# USB_Audio.net
KiCad netlist of a schematic drawn in Altium Designer
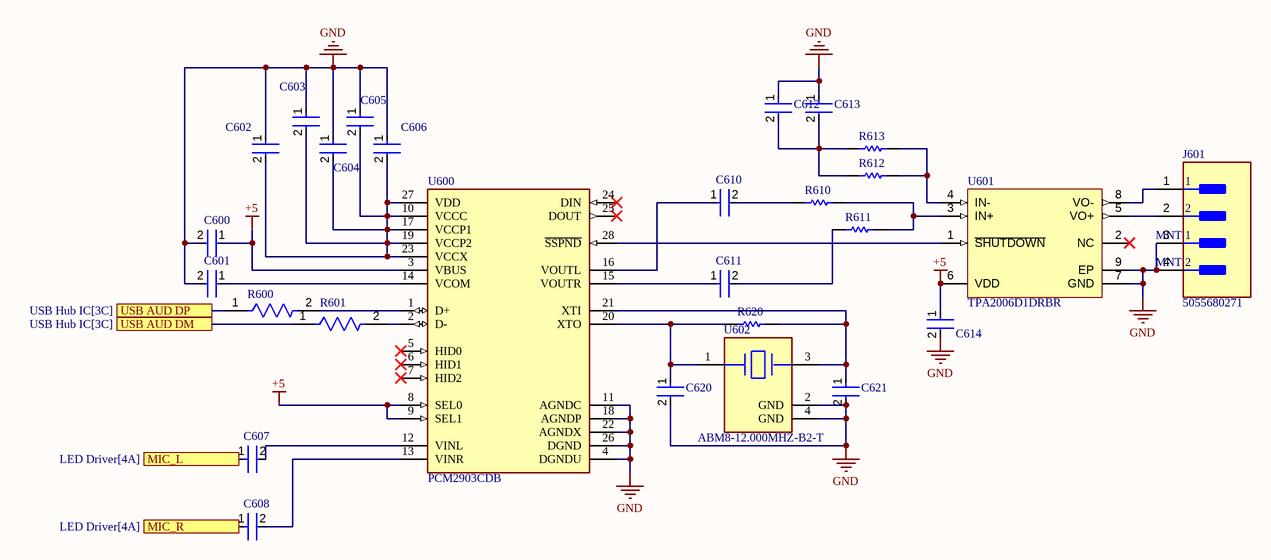
[diagram p0: USB Audio.SchDoc]

(export (version "E")
  (design (tool "Eeschema 10.0.6"))
  (components
    (comp (ref "C600")
      (value "GRM155R70J105KA12D")
      (footprint "FP-GRM155-0_05-MFG")
      (description "Chip Multilayer Ceramic Capacitors for General Purpose, 0402, 1.0uF, X7R, 15%, 10%, 6.3V")
      (fields (field (name "TOLERANCE") "10%"))
      (libsource (lib "Altium Content Vault") (part "02cd4be3c70576c341d710602a673aa"))
    )
    (comp (ref "C601")
      (value "GRM155R70J105KA12D")
      (footprint "FP-GRM155-0_05-MFG")
      (description "Chip Multilayer Ceramic Capacitors for General Purpose, 0402, 1.0uF, X7R, 15%, 10%, 6.3V")
      (fields (field (name "TOLERANCE") "10%"))
      (libsource (lib "Altium Content Vault") (part "02cd4be3c70576c341d710602a673aa"))
    )
    (comp (ref "C602")
      (value "GRM155R70J105KA12D")
      (footprint "FP-GRM155-0_05-MFG")
      (description "Chip Multilayer Ceramic Capacitors for General Purpose, 0402, 1.0uF, X7R, 15%, 10%, 6.3V")
      (fields (field (name "TOLERANCE") "10%"))
      (libsource (lib "Altium Content Vault") (part "02cd4be3c70576c341d710602a673aa"))
    )
    (comp (ref "C603")
      (value "GRM155R70J105KA12D")
      (footprint "FP-GRM155-0_05-MFG")
      (description "Chip Multilayer Ceramic Capacitors for General Purpose, 0402, 1.0uF, X7R, 15%, 10%, 6.3V")
      (fields (field (name "TOLERANCE") "10%"))
      (libsource (lib "Altium Content Vault") (part "02cd4be3c70576c341d710602a673aa"))
    )
    (comp (ref "C604")
      (value "GRM155R70J105KA12D")
      (footprint "FP-GRM155-0_05-MFG")
      (description "Chip Multilayer Ceramic Capacitors for General Purpose, 0402, 1.0uF, X7R, 15%, 10%, 6.3V")
      (fields (field (name "TOLERANCE") "10%"))
      (libsource (lib "Altium Content Vault") (part "02cd4be3c70576c341d710602a673aa"))
    )
    (comp (ref "C605")
      (value "GRM155R70J105KA12D")
      (footprint "FP-GRM155-0_05-MFG")
      (description "Chip Multilayer Ceramic Capacitors for General Purpose, 0402, 1.0uF, X7R, 15%, 10%, 6.3V")
      (fields (field (name "TOLERANCE") "10%"))
      (libsource (lib "Altium Content Vault") (part "02cd4be3c70576c341d710602a673aa"))
    )
    (comp (ref "C606")
      (value "GRM155R70J105KA12D")
      (footprint "FP-GRM155-0_05-MFG")
      (description "Chip Multilayer Ceramic Capacitors for General Purpose, 0402, 1.0uF, X7R, 15%, 10%, 6.3V")
      (fields (field (name "TOLERANCE") "10%"))
      (libsource (lib "Altium Content Vault") (part "02cd4be3c70576c341d710602a673aa"))
    )
    (comp (ref "C607")
      (value "C0402C103K3RACTU")
      (footprint "FP-C0402-BB-MFG")
      (description "Multilayer Ceramic Capacitors MLCC - SMD/SMT 25volts 10000pF X7R 10%")
      (fields
        (field (name "OCTOPART") "https://octopart.com/c0402c103k3ractu-kemet-129636")
        (field (name "TOLERANCE") "0.1")
      )
      (libsource (lib "Altium Content Vault") (part "b4654b650e69147ec39a6b967a45e02"))
    )
    (comp (ref "C608")
      (value "C0402C103K3RACTU")
      (footprint "FP-C0402-BB-MFG")
      (description "Multilayer Ceramic Capacitors MLCC - SMD/SMT 25volts 10000pF X7R 10%")
      (fields
        (field (name "OCTOPART") "https://octopart.com/c0402c103k3ractu-kemet-129636")
        (field (name "TOLERANCE") "0.1")
      )
      (libsource (lib "Altium Content Vault") (part "b4654b650e69147ec39a6b967a45e02"))
    )
    (comp (ref "C610")
      (value "C0402C103K3RACTU")
      (footprint "FP-C0402-BB-MFG")
      (description "Multilayer Ceramic Capacitors MLCC - SMD/SMT 25volts 10000pF X7R 10%")
      (fields
        (field (name "OCTOPART") "https://octopart.com/c0402c103k3ractu-kemet-129636")
        (field (name "TOLERANCE") "0.1")
      )
      (libsource (lib "Altium Content Vault") (part "b4654b650e69147ec39a6b967a45e02"))
    )
    (comp (ref "C611")
      (value "C0402C103K3RACTU")
      (footprint "FP-C0402-BB-MFG")
      (description "Multilayer Ceramic Capacitors MLCC - SMD/SMT 25volts 10000pF X7R 10%")
      (fields
        (field (name "OCTOPART") "https://octopart.com/c0402c103k3ractu-kemet-129636")
        (field (name "TOLERANCE") "0.1")
      )
      (libsource (lib "Altium Content Vault") (part "b4654b650e69147ec39a6b967a45e02"))
    )
    (comp (ref "C612")
      (value "C0402C103K3RACTU")
      (footprint "FP-C0402-BB-MFG")
      (description "Multilayer Ceramic Capacitors MLCC - SMD/SMT 25volts 10000pF X7R 10%")
      (fields
        (field (name "OCTOPART") "https://octopart.com/c0402c103k3ractu-kemet-129636")
        (field (name "TOLERANCE") "0.1")
      )
      (libsource (lib "Altium Content Vault") (part "b4654b650e69147ec39a6b967a45e02"))
    )
    (comp (ref "C613")
      (value "C0402C103K3RACTU")
      (footprint "FP-C0402-BB-MFG")
      (description "Multilayer Ceramic Capacitors MLCC - SMD/SMT 25volts 10000pF X7R 10%")
      (fields
        (field (name "OCTOPART") "https://octopart.com/c0402c103k3ractu-kemet-129636")
        (field (name "TOLERANCE") "0.1")
      )
      (libsource (lib "Altium Content Vault") (part "b4654b650e69147ec39a6b967a45e02"))
    )
    (comp (ref "C614")
      (value "GRM155R70J105KA12D")
      (footprint "FP-GRM155-0_05-MFG")
      (description "Chip Multilayer Ceramic Capacitors for General Purpose, 0402, 1.0uF, X7R, 15%, 10%, 6.3V")
      (fields (field (name "TOLERANCE") "10%"))
      (libsource (lib "Altium Content Vault") (part "02cd4be3c70576c341d710602a673aa"))
    )
    (comp (ref "C620")
      (value "GJM1555C1H180JB01D")
      (footprint "FP-GJM155-0_05-IPC_B")
      (description "Multi-Layer Ceramic Capacitor 18pF C0G  ±5% 0402 Paper T/R")
      (fields (field (name "VOLTAGE") "50V") (field (name "TOLERANCE") "5%"))
      (libsource (lib "Altium Content Vault") (part "02cd4be3c70576c341d710602a673aa"))
    )
    (comp (ref "C621")
      (value "GJM1555C1H180JB01D")
      (footprint "FP-GJM155-0_05-IPC_B")
      (description "Multi-Layer Ceramic Capacitor 18pF C0G  ±5% 0402 Paper T/R")
      (fields (field (name "VOLTAGE") "50V") (field (name "TOLERANCE") "5%"))
      (libsource (lib "Altium Content Vault") (part "02cd4be3c70576c341d710602a673aa"))
    )
    (comp (ref "J601")
      (value "5055680271")
      (footprint "FP-5055680271-MFG")
      (description "CONN HEADER SMD 2POS 1.25MM")
      (fields
        (field (name "OCTOPART") "https://octopart.com/505568-0271-molex-84869617")
        (field (name "MANUFACTURER") "molex")
      )
      (libsource (lib "Altium Content Vault") (part "6ebc6fc72a9fd5a6899c7600f385cff"))
    )
    (comp (ref "R600")
      (value "ERJ-2RKF27R0X")
      (footprint "FP-ERJ2R-IPC_B")
      (description "RES SMD 27 OHM 1% 1/10W 0402")
      (fields (field (name "TOLERANCE") "1%"))
      (libsource (lib "Altium Content Vault") (part "8db39607336c341a927600551d01821"))
    )
    (comp (ref "R601")
      (value "ERJ-2RKF27R0X")
      (footprint "FP-ERJ2R-IPC_B")
      (description "RES SMD 27 OHM 1% 1/10W 0402")
      (fields (field (name "TOLERANCE") "1%"))
      (libsource (lib "Altium Content Vault") (part "8db39607336c341a927600551d01821"))
    )
    (comp (ref "R610")
      (value "ERA2AEB683X")
      (footprint "RESC1005X40X25LL10T10")
      (fields (field (name "MANUFACTURER") "Panasonic"))
      (libsource (lib "Altium Content Vault") (part "RES"))
    )
    (comp (ref "R611")
      (value "ERA2AEB683X")
      (footprint "RESC1005X40X25LL10T10")
      (fields (field (name "MANUFACTURER") "Panasonic"))
      (libsource (lib "Altium Content Vault") (part "RES"))
    )
    (comp (ref "R612")
      (value "ERA2AEB683X")
      (footprint "RESC1005X40X25LL10T10")
      (fields (field (name "MANUFACTURER") "Panasonic"))
      (libsource (lib "Altium Content Vault") (part "RES"))
    )
    (comp (ref "R613")
      (value "ERA2AEB683X")
      (footprint "RESC1005X40X25LL10T10")
      (fields (field (name "MANUFACTURER") "Panasonic"))
      (libsource (lib "Altium Content Vault") (part "RES"))
    )
    (comp (ref "R620")
      (value "ERJ-2RKF1004X")
      (footprint "RESC1005X40X25LL05T05")
      (description "Chip Resistor, 1 MOhm, +/- 1%, 100 mW, -55 to 155 degC, 0402 (1005 Metric), RoHS, Tape and Reel")
      (fields (field (name "TOLERANCE") "1%") (field (name "MANUFACTURER") "Basic Passives"))
      (libsource (lib "Altium Content Vault") (part "RES-2"))
    )
    (comp (ref "U600")
      (value "PCM2903CDB")
      (footprint "FP-DB0028A-IPC_A")
      (description "IC STERO AUD CODEC W/USB 28SSOP")
      (libsource (lib "Altium Content Vault") (part "e2d535d5cf0c7fcd44f2eec1acaa462"))
    )
    (comp (ref "U601")
      (value "TPA2006D1DRBR")
      (footprint "DRB0008A_V")
      (fields (field (name "MANUFACTURER") "Texas Instruments"))
      (libsource (lib "Altium Content Vault") (part "TI-TPA2005_6D1XDXX8-TP"))
    )
    (comp (ref "U602")
      (value "ABM8-12.000MHZ-B2-T")
      (footprint "FP-ABM8-MFG")
      (description "Crystal 12MHz ±20ppm 18pF SMD-4 3.2mm x 2.5mm")
      (fields (field (name "TOLERANCE") "20ppm"))
      (libsource (lib "Altium Content Vault") (part "dfdb7f9a12507849fb681da9a70121c"))
    )
  )
  (nets
    (net (code "1") (name "+5") (class "Default")
      (node (ref "C600") (pin "1") (pinfunction "1_1") (pintype "passive"))
      (node (ref "C614") (pin "1") (pinfunction "1_1") (pintype "passive"))
      (node (ref "U600") (pin "3") (pinfunction "VBUS_3") (pintype "power_in"))
      (node (ref "U600") (pin "8") (pinfunction "SEL0_8") (pintype "input"))
      (node (ref "U600") (pin "9") (pinfunction "SEL1_9") (pintype "input"))
      (node (ref "U601") (pin "6") (pinfunction "VDD_6") (pintype "power_in"))
    )
    (net (code "2") (name "/MIC_L") (class "Default")
      (node (ref "C607") (pin "1") (pinfunction "1_1") (pintype "passive"))
    )
    (net (code "3") (name "/MIC_R") (class "Default")
      (node (ref "C608") (pin "1") (pinfunction "1_1") (pintype "passive"))
    )
    (net (code "4") (name "/USB AUD DM") (class "Default")
      (node (ref "R601") (pin "1") (pinfunction "1_1") (pintype "passive"))
    )
    (net (code "5") (name "/USB AUD DP") (class "Default")
      (node (ref "R600") (pin "1") (pinfunction "1_1") (pintype "passive"))
    )
    (net (code "6") (name "GND") (class "Default")
      (node (ref "C600") (pin "2") (pinfunction "2_2") (pintype "passive"))
      (node (ref "C601") (pin "2") (pinfunction "2_2") (pintype "passive"))
      (node (ref "C602") (pin "1") (pinfunction "1_1") (pintype "passive"))
      (node (ref "C603") (pin "1") (pinfunction "1_1") (pintype "passive"))
      (node (ref "C604") (pin "1") (pinfunction "1_1") (pintype "passive"))
      (node (ref "C605") (pin "1") (pinfunction "1_1") (pintype "passive"))
      (node (ref "C606") (pin "1") (pinfunction "1_1") (pintype "passive"))
      (node (ref "C612") (pin "1") (pinfunction "1_1") (pintype "passive"))
      (node (ref "C613") (pin "1") (pinfunction "1_1") (pintype "passive"))
      (node (ref "C614") (pin "2") (pinfunction "2_2") (pintype "passive"))
      (node (ref "C620") (pin "2") (pinfunction "2_2") (pintype "passive"))
      (node (ref "C621") (pin "2") (pinfunction "2_2") (pintype "passive"))
      (node (ref "J601") (pin "3") (pinfunction "MNT_1_3") (pintype "passive"))
      (node (ref "J601") (pin "4") (pinfunction "MNT_2_4") (pintype "passive"))
      (node (ref "U600") (pin "11") (pinfunction "AGNDC_11") (pintype "power_in"))
      (node (ref "U600") (pin "18") (pinfunction "AGNDP_18") (pintype "power_in"))
      (node (ref "U600") (pin "22") (pinfunction "AGNDX_22") (pintype "power_in"))
      (node (ref "U600") (pin "26") (pinfunction "DGND_26") (pintype "power_in"))
      (node (ref "U600") (pin "4") (pinfunction "DGNDU_4") (pintype "power_in"))
      (node (ref "U601") (pin "7") (pinfunction "GND_7") (pintype "power_in"))
      (node (ref "U601") (pin "9") (pinfunction "EP_9") (pintype "power_in"))
      (node (ref "U602") (pin "2") (pinfunction "GND_2") (pintype "power_in"))
      (node (ref "U602") (pin "4") (pinfunction "GND_4") (pintype "power_in"))
    )
    (net (code "7") (name "Net-(C610-Pad2)") (class "Default")
      (node (ref "C610") (pin "2") (pinfunction "2_2") (pintype "passive"))
      (node (ref "R610") (pin "1") (pinfunction "1_1") (pintype "passive"))
    )
    (net (code "8") (name "Net-(C611-Pad2)") (class "Default")
      (node (ref "C611") (pin "2") (pinfunction "2_2") (pintype "passive"))
      (node (ref "R611") (pin "1") (pinfunction "1_1") (pintype "passive"))
    )
    (net (code "9") (name "Net-(C612-Pad2)") (class "Default")
      (node (ref "C612") (pin "2") (pinfunction "2_2") (pintype "passive"))
      (node (ref "C613") (pin "2") (pinfunction "2_2") (pintype "passive"))
      (node (ref "R612") (pin "1") (pinfunction "1_1") (pintype "passive"))
      (node (ref "R613") (pin "1") (pinfunction "1_1") (pintype "passive"))
    )
    (net (code "10") (name "Net-(U600-D+)") (class "Default")
      (node (ref "R600") (pin "2") (pinfunction "2_2") (pintype "passive"))
      (node (ref "U600") (pin "1") (pinfunction "D+_1") (pintype "bidirectional"))
    )
    (net (code "11") (name "Net-(U600-D-)") (class "Default")
      (node (ref "R601") (pin "2") (pinfunction "2_2") (pintype "passive"))
      (node (ref "U600") (pin "2") (pinfunction "D-_2") (pintype "bidirectional"))
    )
    (net (code "12") (name "Net-(U600-VCCC)") (class "Default")
      (node (ref "C602") (pin "2") (pinfunction "2_2") (pintype "passive"))
      (node (ref "C603") (pin "2") (pinfunction "2_2") (pintype "passive"))
      (node (ref "C604") (pin "2") (pinfunction "2_2") (pintype "passive"))
      (node (ref "C605") (pin "2") (pinfunction "2_2") (pintype "passive"))
      (node (ref "C606") (pin "2") (pinfunction "2_2") (pintype "passive"))
      (node (ref "U600") (pin "10") (pinfunction "VCCC_10") (pintype "power_in"))
      (node (ref "U600") (pin "17") (pinfunction "VCCP1_17") (pintype "passive"))
      (node (ref "U600") (pin "19") (pinfunction "VCCP2_19") (pintype "power_in"))
      (node (ref "U600") (pin "23") (pinfunction "VCCX_23") (pintype "power_in"))
      (node (ref "U600") (pin "27") (pinfunction "VDD_27") (pintype "power_in"))
    )
    (net (code "13") (name "Net-(U600-VCOM)") (class "Default")
      (node (ref "C601") (pin "1") (pinfunction "1_1") (pintype "passive"))
      (node (ref "U600") (pin "14") (pinfunction "VCOM_14") (pintype "passive"))
    )
    (net (code "14") (name "Net-(U600-VINL)") (class "Default")
      (node (ref "C607") (pin "2") (pinfunction "2_2") (pintype "passive"))
      (node (ref "U600") (pin "12") (pinfunction "VINL_12") (pintype "passive"))
    )
    (net (code "15") (name "Net-(U600-VINR)") (class "Default")
      (node (ref "C608") (pin "2") (pinfunction "2_2") (pintype "passive"))
      (node (ref "U600") (pin "13") (pinfunction "VINR_13") (pintype "passive"))
    )
    (net (code "16") (name "Net-(U600-VOUTL)") (class "Default")
      (node (ref "C610") (pin "1") (pinfunction "1_1") (pintype "passive"))
      (node (ref "U600") (pin "16") (pinfunction "VOUTL_16") (pintype "passive"))
    )
    (net (code "17") (name "Net-(U600-VOUTR)") (class "Default")
      (node (ref "C611") (pin "1") (pinfunction "1_1") (pintype "passive"))
      (node (ref "U600") (pin "15") (pinfunction "VOUTR_15") (pintype "passive"))
    )
    (net (code "18") (name "Net-(U600-XTI)") (class "Default")
      (node (ref "C621") (pin "1") (pinfunction "1_1") (pintype "passive"))
      (node (ref "R620") (pin "2") (pinfunction "2_2") (pintype "passive"))
      (node (ref "U600") (pin "21") (pinfunction "XTI_21") (pintype "passive"))
      (node (ref "U602") (pin "3") (pinfunction "3_3") (pintype "passive"))
    )
    (net (code "19") (name "Net-(U600-XTO)") (class "Default")
      (node (ref "C620") (pin "1") (pinfunction "1_1") (pintype "passive"))
      (node (ref "R620") (pin "1") (pinfunction "1_1") (pintype "passive"))
      (node (ref "U600") (pin "20") (pinfunction "XTO_20") (pintype "passive"))
      (node (ref "U602") (pin "1") (pinfunction "1_1") (pintype "passive"))
    )
    (net (code "20") (name "Net-(U600-~{SSPND})") (class "Default")
      (node (ref "U600") (pin "28") (pinfunction "~{SSPND}_28") (pintype "input"))
      (node (ref "U601") (pin "1") (pinfunction "~{SHUTDOWN}_1") (pintype "input"))
    )
    (net (code "21") (name "Net-(U601-IN+)") (class "Default")
      (node (ref "R610") (pin "2") (pinfunction "2_2") (pintype "passive"))
      (node (ref "R611") (pin "2") (pinfunction "2_2") (pintype "passive"))
      (node (ref "U601") (pin "3") (pinfunction "IN+_3") (pintype "input"))
    )
    (net (code "22") (name "Net-(U601-IN-)") (class "Default")
      (node (ref "R612") (pin "2") (pinfunction "2_2") (pintype "passive"))
      (node (ref "R613") (pin "2") (pinfunction "2_2") (pintype "passive"))
      (node (ref "U601") (pin "4") (pinfunction "IN-_4") (pintype "input"))
    )
    (net (code "23") (name "Net-(U601-VO+)") (class "Default")
      (node (ref "J601") (pin "2") (pinfunction "2_2") (pintype "passive"))
      (node (ref "U601") (pin "5") (pinfunction "VO+_5") (pintype "output"))
    )
    (net (code "24") (name "Net-(U601-VO-)") (class "Default")
      (node (ref "J601") (pin "1") (pinfunction "1_1") (pintype "passive"))
      (node (ref "U601") (pin "8") (pinfunction "VO-_8") (pintype "output"))
    )
    (net (code "25") (name "unconnected-(U600-DIN-Pad24)") (class "Default")
      (node (ref "U600") (pin "24") (pinfunction "DIN_24") (pintype "input+no_connect"))
    )
    (net (code "26") (name "unconnected-(U600-DOUT-Pad25)") (class "Default")
      (node (ref "U600") (pin "25") (pinfunction "DOUT_25") (pintype "output+no_connect"))
    )
    (net (code "27") (name "unconnected-(U600-HID0-Pad5)") (class "Default")
      (node (ref "U600") (pin "5") (pinfunction "HID0_5") (pintype "input+no_connect"))
    )
    (net (code "28") (name "unconnected-(U600-HID1-Pad6)") (class "Default")
      (node (ref "U600") (pin "6") (pinfunction "HID1_6") (pintype "input+no_connect"))
    )
    (net (code "29") (name "unconnected-(U600-HID2-Pad7)") (class "Default")
      (node (ref "U600") (pin "7") (pinfunction "HID2_7") (pintype "input+no_connect"))
    )
    (net (code "30") (name "unconnected-(U601-NC-Pad2)") (class "Default")
      (node (ref "U601") (pin "2") (pinfunction "NC_2") (pintype "passive+no_connect"))
    )
  )
)
